# rgb.net
KiCad netlist of a schematic drawn in EAGLE
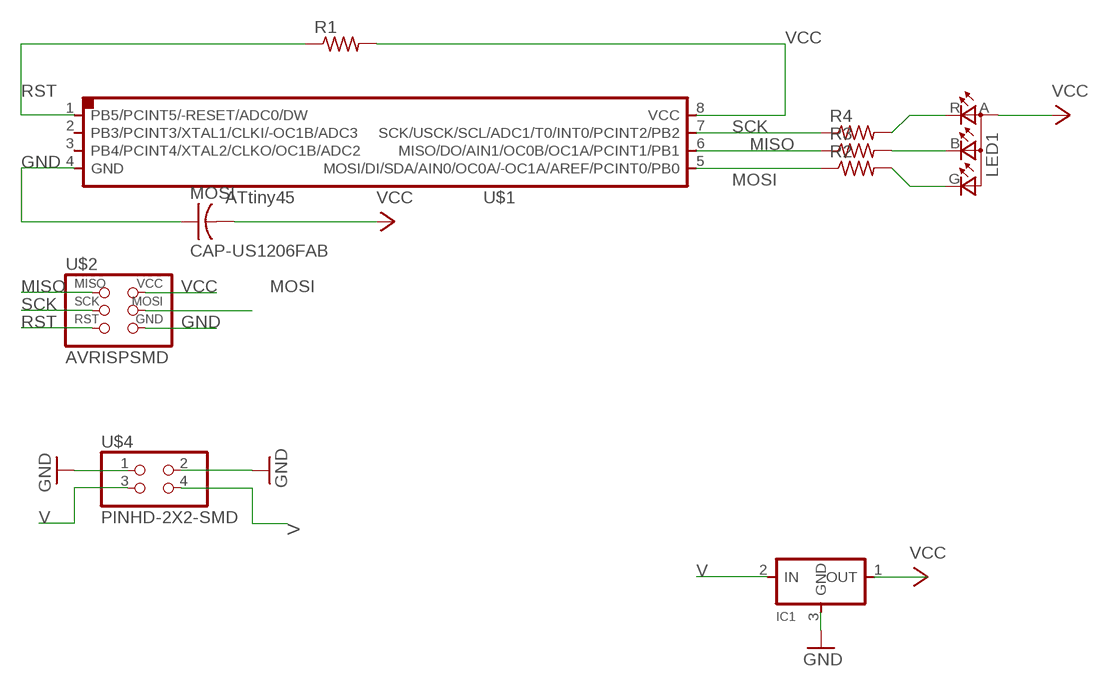
[diagram p0: schematic, sheet 1]

(export (version "E")
  (design (tool "Eeschema 10.0.6"))
  (components
    (comp (ref "IC1")
      (value "REGULATORSOT23")
      (footprint "eagle-import:SOT23")
      (libsource (lib "eagle-import") (part "REGULATORSOT23"))
    )
    (comp (ref "LED1")
      (value "LEDRGBOLD")
      (footprint "eagle-import:P-LCC-4-3")
      (libsource (lib "eagle-import") (part "LEDRGBOLD"))
    )
    (comp (ref "MOSI")
      (value "CAP-US1206FAB")
      (footprint "eagle-import:C1206FAB")
      (libsource (lib "eagle-import") (part "CAP-US1206FAB"))
    )
    (comp (ref "R1")
      (value "RES-US1206FAB")
      (footprint "eagle-import:R1206FAB")
      (libsource (lib "eagle-import") (part "RES-US1206FAB"))
    )
    (comp (ref "R2")
      (value "RES-US1206FAB")
      (footprint "eagle-import:R1206FAB")
      (libsource (lib "eagle-import") (part "RES-US1206FAB"))
    )
    (comp (ref "R3")
      (value "RES-US1206FAB")
      (footprint "eagle-import:R1206FAB")
      (libsource (lib "eagle-import") (part "RES-US1206FAB"))
    )
    (comp (ref "R4")
      (value "RES-US1206FAB")
      (footprint "eagle-import:R1206FAB")
      (libsource (lib "eagle-import") (part "RES-US1206FAB"))
    )
    (comp (ref "U$1")
      (value "ATTINY45SI")
      (footprint "eagle-import:SOIC8")
      (libsource (lib "eagle-import") (part "ATTINY45SI"))
    )
    (comp (ref "U$2")
      (value "AVRISPSMD")
      (footprint "eagle-import:2X03SMD")
      (libsource (lib "eagle-import") (part "AVRISPSMD"))
    )
    (comp (ref "U$4")
      (value "PINHD-2X2-SMD")
      (footprint "eagle-import:2X02SMD")
      (libsource (lib "eagle-import") (part "PINHD-2X2-SMD"))
    )
  )
  (nets
    (net (code "1") (name "/MISO") (class "Default")
      (node (ref "R3") (pin "1") (pinfunction "1_1") (pintype "passive"))
      (node (ref "U$1") (pin "6") (pinfunction "MISO/DO/AIN1/OC0B/OC1A/PCINT1/PB1_6") (pintype "bidirectional"))
      (node (ref "U$2") (pin "1") (pinfunction "MISO_1") (pintype "passive"))
    )
    (net (code "2") (name "/MOSI") (class "Default")
      (node (ref "R2") (pin "1") (pinfunction "1_1") (pintype "passive"))
      (node (ref "U$1") (pin "5") (pinfunction "MOSI/DI/SDA/AIN0/OC0A/-OC1A/AREF/PCINT0/PB0_5") (pintype "bidirectional"))
      (node (ref "U$2") (pin "4") (pinfunction "MOSI_4") (pintype "passive"))
    )
    (net (code "3") (name "/RST") (class "Default")
      (node (ref "R1") (pin "1") (pinfunction "1_1") (pintype "passive"))
      (node (ref "U$1") (pin "1") (pinfunction "PB5/PCINT5/-RESET/ADC0/DW_1") (pintype "bidirectional"))
      (node (ref "U$2") (pin "5") (pinfunction "RST_5") (pintype "passive"))
    )
    (net (code "4") (name "/SCK") (class "Default")
      (node (ref "R4") (pin "1") (pinfunction "1_1") (pintype "passive"))
      (node (ref "U$1") (pin "7") (pinfunction "SCK/USCK/SCL/ADC1/T0/INT0/PCINT2/PB2_7") (pintype "bidirectional"))
      (node (ref "U$2") (pin "3") (pinfunction "SCK_3") (pintype "passive"))
    )
    (net (code "5") (name "/V") (class "Default")
      (node (ref "IC1") (pin "2") (pinfunction "IN_2") (pintype "bidirectional"))
      (node (ref "U$4") (pin "3") (pinfunction "3_3") (pintype "passive"))
      (node (ref "U$4") (pin "4") (pinfunction "4_4") (pintype "passive"))
    )
    (net (code "6") (name "GND") (class "Default")
      (node (ref "IC1") (pin "3") (pinfunction "GND_3") (pintype "bidirectional"))
      (node (ref "MOSI") (pin "1") (pinfunction "1_1") (pintype "passive"))
      (node (ref "U$1") (pin "4") (pinfunction "GND_4") (pintype "bidirectional"))
      (node (ref "U$2") (pin "6") (pinfunction "GND_6") (pintype "passive"))
      (node (ref "U$4") (pin "1") (pinfunction "1_1") (pintype "passive"))
      (node (ref "U$4") (pin "2") (pinfunction "2_2") (pintype "passive"))
    )
    (net (code "7") (name "Net-(LED1-CBLUE)") (class "Default")
      (node (ref "LED1") (pin "B") (pinfunction "CBLUE_B") (pintype "passive"))
      (node (ref "R3") (pin "2") (pinfunction "2_2") (pintype "passive"))
    )
    (net (code "8") (name "Net-(LED1-CGREEN)") (class "Default")
      (node (ref "LED1") (pin "G") (pinfunction "CGREEN_G") (pintype "passive"))
      (node (ref "R2") (pin "2") (pinfunction "2_2") (pintype "passive"))
    )
    (net (code "9") (name "Net-(LED1-CRED)") (class "Default")
      (node (ref "LED1") (pin "R") (pinfunction "CRED_R") (pintype "passive"))
      (node (ref "R4") (pin "2") (pinfunction "2_2") (pintype "passive"))
    )
    (net (code "10") (name "VCC") (class "Default")
      (node (ref "LED1") (pin "A") (pinfunction "A2_A") (pintype "passive"))
      (node (ref "MOSI") (pin "2") (pinfunction "2_2") (pintype "passive"))
      (node (ref "R1") (pin "2") (pinfunction "2_2") (pintype "passive"))
      (node (ref "U$1") (pin "8") (pinfunction "VCC_8") (pintype "bidirectional"))
      (node (ref "U$2") (pin "2") (pinfunction "VCC_2") (pintype "passive"))
    )
    (net (code "11") (name "unconnected-(IC1-OUT-Pad1)") (class "Default")
      (node (ref "IC1") (pin "1") (pinfunction "OUT_1") (pintype "bidirectional"))
    )
    (net (code "12") (name "unconnected-(U$1-PB3{slash}PCINT3{slash}XTAL1{slash}CLKI{slash}-OC1B{slash}ADC3-Pad2)") (class "Default")
      (node (ref "U$1") (pin "2") (pinfunction "PB3/PCINT3/XTAL1/CLKI/-OC1B/ADC3_2") (pintype "bidirectional"))
    )
    (net (code "13") (name "unconnected-(U$1-PB4{slash}PCINT4{slash}XTAL2{slash}CLKO{slash}OC1B{slash}ADC2-Pad3)") (class "Default")
      (node (ref "U$1") (pin "3") (pinfunction "PB4/PCINT4/XTAL2/CLKO/OC1B/ADC2_3") (pintype "bidirectional"))
    )
  )
)
